# CPU_ROM.net
KiCad netlist of a schematic drawn in Altium Designer
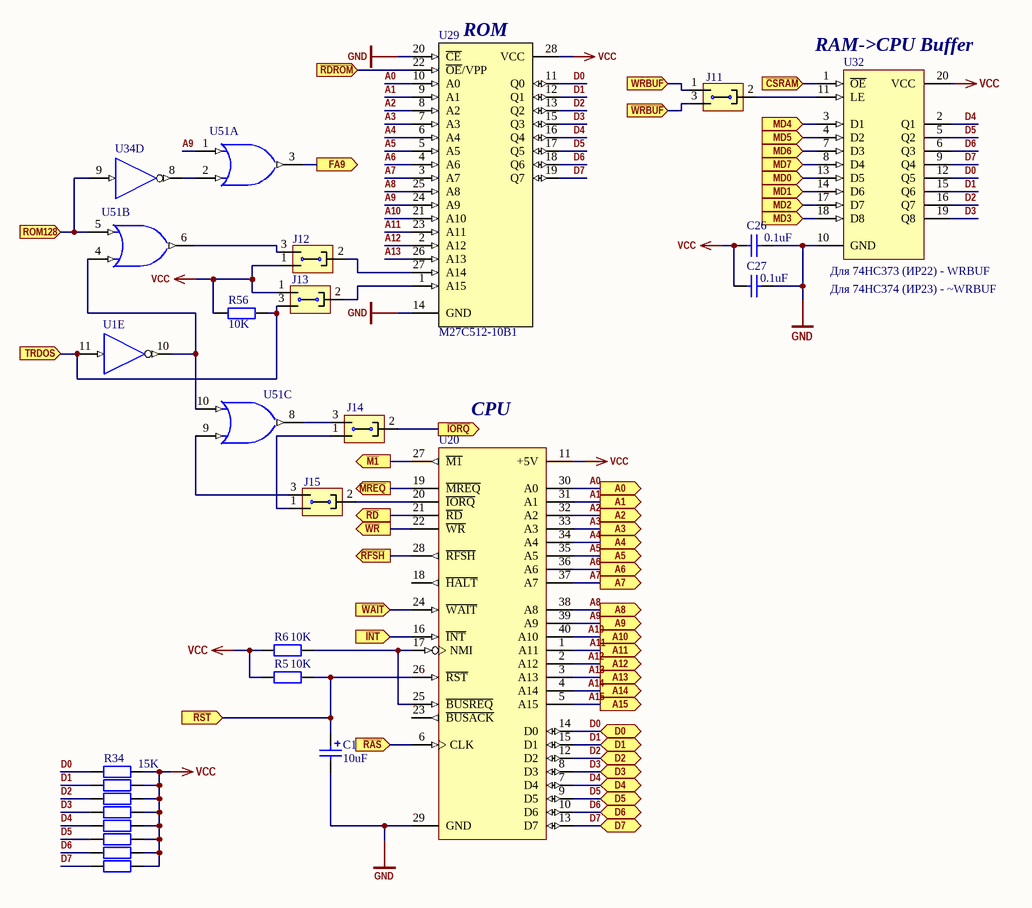
[diagram p0: CPU_ROM.SchDoc]

(export (version "E")
  (design (tool "Eeschema 10.0.6"))
  (components
    (comp (ref "C1")
      (value "10uF")
      (footprint "Lenin:JRB-5D")
      (description "Polarized Capacitor (Radial)")
      (fields (field (name "Comment") "Cap Pol1") (field (name "PUBLISHER") "Altium Limited"))
      (libsource (lib "Lenin") (part "Cap Pol1"))
    )
    (comp (ref "C26")
      (value "0.1uF")
      (footprint "RAD-0.3")
      (description "Capacitor")
      (fields (field (name "Comment") "Cap") (field (name "PUBLISHER") "Altium Limited"))
      (libsource (lib "Lenin") (part "Cap"))
    )
    (comp (ref "C27")
      (value "0.1uF")
      (footprint "RAD-0.3")
      (description "Capacitor")
      (fields (field (name "Comment") "Cap") (field (name "PUBLISHER") "Altium Limited"))
      (libsource (lib "Lenin") (part "Cap"))
    )
    (comp (ref "J11")
      (value "Jump3")
      (footprint "Miscellaneous Connectors:MHDR1X3")
      (libsource (lib "") (part "Jump3_1"))
    )
    (comp (ref "J12")
      (value "Jump3")
      (footprint "Miscellaneous Connectors:MHDR1X3")
      (libsource (lib "Lenin") (part "Jump3"))
    )
    (comp (ref "J13")
      (value "Jump3")
      (footprint "Miscellaneous Connectors:MHDR1X3")
      (libsource (lib "") (part "Jump3_1"))
    )
    (comp (ref "J14")
      (value "Jump3")
      (footprint "Miscellaneous Connectors:MHDR1X3")
      (libsource (lib "Lenin") (part "Jump3"))
    )
    (comp (ref "J15")
      (value "Jump3")
      (footprint "Miscellaneous Connectors:MHDR1X3")
      (libsource (lib "Lenin") (part "Jump3"))
    )
    (comp (ref "R5")
      (value "10K")
      (footprint "Lenin:AXIAL-0.4")
      (description "Resistor")
      (fields (field (name "PUBLISHER") "Altium Limited"))
      (libsource (lib "Lenin") (part "Res2"))
    )
    (comp (ref "R6")
      (value "10K")
      (footprint "Lenin:AXIAL-0.4")
      (description "Resistor")
      (fields (field (name "PUBLISHER") "Altium Limited"))
      (libsource (lib "") (part "Res2_1"))
    )
    (comp (ref "R34")
      (value "15K")
      (footprint "Lenin:AXIAL-0.4")
      (description "Resistor")
      (fields (field (name "PUBLISHER") "Altium Limited"))
      (libsource (lib "Lenin") (part "Res2"))
    )
    (comp (ref "R35")
      (value "~")
      (footprint "Lenin:AXIAL-0.4")
      (description "Resistor")
      (fields (field (name "PUBLISHER") "Altium Limited"))
      (libsource (lib "Lenin") (part "Res2"))
    )
    (comp (ref "R37")
      (value "~")
      (footprint "Lenin:AXIAL-0.4")
      (description "Resistor")
      (fields (field (name "PUBLISHER") "Altium Limited"))
      (libsource (lib "Lenin") (part "Res2"))
    )
    (comp (ref "R39")
      (value "~")
      (footprint "Lenin:AXIAL-0.4")
      (description "Resistor")
      (fields (field (name "PUBLISHER") "Altium Limited"))
      (libsource (lib "Lenin") (part "Res2"))
    )
    (comp (ref "R41")
      (value "~")
      (footprint "Lenin:AXIAL-0.4")
      (description "Resistor")
      (fields (field (name "PUBLISHER") "Altium Limited"))
      (libsource (lib "Lenin") (part "Res2"))
    )
    (comp (ref "R43")
      (value "~")
      (footprint "Lenin:AXIAL-0.4")
      (description "Resistor")
      (fields (field (name "PUBLISHER") "Altium Limited"))
      (libsource (lib "Lenin") (part "Res2"))
    )
    (comp (ref "R47")
      (value "~")
      (footprint "Lenin:AXIAL-0.4")
      (description "Resistor")
      (fields (field (name "PUBLISHER") "Altium Limited"))
      (libsource (lib "Lenin") (part "Res2"))
    )
    (comp (ref "R48")
      (value "~")
      (footprint "Lenin:AXIAL-0.4")
      (description "Resistor")
      (fields (field (name "PUBLISHER") "Altium Limited"))
      (libsource (lib "Lenin") (part "Res2"))
    )
    (comp (ref "R56")
      (value "10K")
      (footprint "Lenin:AXIAL-0.4")
      (description "Resistor")
      (fields (field (name "PUBLISHER") "Altium Limited"))
      (libsource (lib "Lenin") (part "Res2"))
    )
    (comp (ref "U1")
      (value "~")
      (footprint "N014")
      (description "Hex Inverter")
      (fields (field (name "PUBLISHER") "Altium Limited"))
      (libsource (lib "TI Logic Gate 2") (part "SN74HC04N"))
    )
    (comp (ref "U20")
      (value "Z84C0004PEC")
      (footprint "PDIP40")
      (description "CMOS 8-Bit Microprocessor")
      (fields (field (name "PUBLISHER") "Altium Limited"))
      (libsource (lib "Zilog Microprocessor 8-Bit") (part "Z84C0004PEC"))
    )
    (comp (ref "U29")
      (value "M27C512-10B1")
      (footprint "PDIP28")
      (description "512 Kbit (64Kb x 8) UV EPROM and OTP EPROM")
      (fields (field (name "PUBLISHER") "Altium Limited"))
      (libsource (lib "ST Memory EPROM 16-512 Kbit") (part "M27C512-10B1"))
    )
    (comp (ref "U32")
      (value "~")
      (footprint "N020")
      (description "Octal Transparent D-Type Latches with 3-State Outputs")
      (fields (field (name "PUBLISHER") "Altium Limited"))
      (libsource (lib "TI Logic Latch") (part "SN74HC373N"))
    )
    (comp (ref "U34")
      (value "~")
      (footprint "N014")
      (description "Hex Inverter")
      (fields (field (name "PUBLISHER") "Altium Limited"))
      (libsource (lib "TI Logic Gate 2") (part "SN74HC04N"))
    )
    (comp (ref "U51")
      (value "SN74HC32N")
      (footprint "N014")
      (description "Quadruple 2-Input Positive-OR Gate")
      (fields (field (name "PUBLISHER") "Altium Limited"))
      (libsource (lib "") (part "SN74HC32N_1"))
    )
  )
  (nets
    (net (code "1") (name "/A0") (class "Default")
      (node (ref "U20") (pin "30") (pinfunction "A0_30") (pintype "tri_state"))
      (node (ref "U29") (pin "10") (pinfunction "A0_10") (pintype "input"))
    )
    (net (code "2") (name "/A1") (class "Default")
      (node (ref "U20") (pin "31") (pinfunction "A1_31") (pintype "tri_state"))
      (node (ref "U29") (pin "9") (pinfunction "A1_9") (pintype "input"))
    )
    (net (code "3") (name "/A2") (class "Default")
      (node (ref "U20") (pin "32") (pinfunction "A2_32") (pintype "tri_state"))
      (node (ref "U29") (pin "8") (pinfunction "A2_8") (pintype "input"))
    )
    (net (code "4") (name "/A3") (class "Default")
      (node (ref "U20") (pin "33") (pinfunction "A3_33") (pintype "tri_state"))
      (node (ref "U29") (pin "7") (pinfunction "A3_7") (pintype "input"))
    )
    (net (code "5") (name "/A4") (class "Default")
      (node (ref "U20") (pin "34") (pinfunction "A4_34") (pintype "tri_state"))
      (node (ref "U29") (pin "6") (pinfunction "A4_6") (pintype "input"))
    )
    (net (code "6") (name "/A5") (class "Default")
      (node (ref "U20") (pin "35") (pinfunction "A5_35") (pintype "tri_state"))
      (node (ref "U29") (pin "5") (pinfunction "A5_5") (pintype "input"))
    )
    (net (code "7") (name "/A6") (class "Default")
      (node (ref "U20") (pin "36") (pinfunction "A6_36") (pintype "tri_state"))
      (node (ref "U29") (pin "4") (pinfunction "A6_4") (pintype "input"))
    )
    (net (code "8") (name "/A7") (class "Default")
      (node (ref "U20") (pin "37") (pinfunction "A7_37") (pintype "tri_state"))
      (node (ref "U29") (pin "3") (pinfunction "A7_3") (pintype "input"))
    )
    (net (code "9") (name "/A8") (class "Default")
      (node (ref "U20") (pin "38") (pinfunction "A8_38") (pintype "tri_state"))
      (node (ref "U29") (pin "25") (pinfunction "A8_25") (pintype "input"))
    )
    (net (code "10") (name "/A9") (class "Default")
      (node (ref "U20") (pin "39") (pinfunction "A9_39") (pintype "tri_state"))
      (node (ref "U29") (pin "24") (pinfunction "A9_24") (pintype "input"))
      (node (ref "U51") (pin "1") (pinfunction "A_1") (pintype "input"))
    )
    (net (code "11") (name "/A10") (class "Default")
      (node (ref "U20") (pin "40") (pinfunction "A10_40") (pintype "tri_state"))
      (node (ref "U29") (pin "21") (pinfunction "A10_21") (pintype "input"))
    )
    (net (code "12") (name "/A11") (class "Default")
      (node (ref "U20") (pin "1") (pinfunction "A11_1") (pintype "tri_state"))
      (node (ref "U29") (pin "23") (pinfunction "A11_23") (pintype "input"))
    )
    (net (code "13") (name "/A12") (class "Default")
      (node (ref "U20") (pin "2") (pinfunction "A12_2") (pintype "tri_state"))
      (node (ref "U29") (pin "2") (pinfunction "A12_2") (pintype "input"))
    )
    (net (code "14") (name "/A13") (class "Default")
      (node (ref "U20") (pin "3") (pinfunction "A13_3") (pintype "tri_state"))
      (node (ref "U29") (pin "26") (pinfunction "A13_26") (pintype "input"))
    )
    (net (code "15") (name "/A14") (class "Default")
      (node (ref "U20") (pin "4") (pinfunction "A14_4") (pintype "tri_state"))
    )
    (net (code "16") (name "/A15") (class "Default")
      (node (ref "U20") (pin "5") (pinfunction "A15_5") (pintype "tri_state"))
    )
    (net (code "17") (name "/D0") (class "Default")
      (node (ref "R34") (pin "1") (pinfunction "1_1") (pintype "passive"))
      (node (ref "U20") (pin "14") (pinfunction "D0_14") (pintype "bidirectional"))
      (node (ref "U29") (pin "11") (pinfunction "Q0_11") (pintype "bidirectional"))
      (node (ref "U32") (pin "12") (pinfunction "Q5_12") (pintype "tri_state"))
    )
    (net (code "18") (name "/D1") (class "Default")
      (node (ref "R35") (pin "1") (pinfunction "1_1") (pintype "passive"))
      (node (ref "U20") (pin "15") (pinfunction "D1_15") (pintype "bidirectional"))
      (node (ref "U29") (pin "12") (pinfunction "Q1_12") (pintype "bidirectional"))
      (node (ref "U32") (pin "15") (pinfunction "Q6_15") (pintype "tri_state"))
    )
    (net (code "19") (name "/D2") (class "Default")
      (node (ref "R37") (pin "1") (pinfunction "1_1") (pintype "passive"))
      (node (ref "U20") (pin "12") (pinfunction "D2_12") (pintype "bidirectional"))
      (node (ref "U29") (pin "13") (pinfunction "Q2_13") (pintype "bidirectional"))
      (node (ref "U32") (pin "16") (pinfunction "Q7_16") (pintype "tri_state"))
    )
    (net (code "20") (name "/D3") (class "Default")
      (node (ref "R39") (pin "1") (pinfunction "1_1") (pintype "passive"))
      (node (ref "U20") (pin "8") (pinfunction "D3_8") (pintype "bidirectional"))
      (node (ref "U29") (pin "15") (pinfunction "Q3_15") (pintype "bidirectional"))
      (node (ref "U32") (pin "19") (pinfunction "Q8_19") (pintype "tri_state"))
    )
    (net (code "21") (name "/D4") (class "Default")
      (node (ref "R41") (pin "1") (pinfunction "1_1") (pintype "passive"))
      (node (ref "U20") (pin "7") (pinfunction "D4_7") (pintype "bidirectional"))
      (node (ref "U29") (pin "16") (pinfunction "Q4_16") (pintype "bidirectional"))
      (node (ref "U32") (pin "2") (pinfunction "Q1_2") (pintype "tri_state"))
    )
    (net (code "22") (name "/D5") (class "Default")
      (node (ref "R43") (pin "1") (pinfunction "1_1") (pintype "passive"))
      (node (ref "U20") (pin "9") (pinfunction "D5_9") (pintype "bidirectional"))
      (node (ref "U29") (pin "17") (pinfunction "Q5_17") (pintype "bidirectional"))
      (node (ref "U32") (pin "5") (pinfunction "Q2_5") (pintype "tri_state"))
    )
    (net (code "23") (name "/D6") (class "Default")
      (node (ref "R47") (pin "1") (pinfunction "1_1") (pintype "passive"))
      (node (ref "U20") (pin "10") (pinfunction "D6_10") (pintype "bidirectional"))
      (node (ref "U29") (pin "18") (pinfunction "Q6_18") (pintype "bidirectional"))
      (node (ref "U32") (pin "6") (pinfunction "Q3_6") (pintype "tri_state"))
    )
    (net (code "24") (name "/D7") (class "Default")
      (node (ref "R48") (pin "1") (pinfunction "1_1") (pintype "passive"))
      (node (ref "U20") (pin "13") (pinfunction "D7_13") (pintype "bidirectional"))
      (node (ref "U29") (pin "19") (pinfunction "Q7_19") (pintype "bidirectional"))
      (node (ref "U32") (pin "9") (pinfunction "Q4_9") (pintype "tri_state"))
    )
    (net (code "25") (name "/FA9") (class "Default")
      (node (ref "U51") (pin "3") (pinfunction "Y_3") (pintype "output"))
    )
    (net (code "26") (name "/MD0") (class "Default")
      (node (ref "U32") (pin "13") (pinfunction "D5_13") (pintype "input"))
    )
    (net (code "27") (name "/MD1") (class "Default")
      (node (ref "U32") (pin "14") (pinfunction "D6_14") (pintype "input"))
    )
    (net (code "28") (name "/MD2") (class "Default")
      (node (ref "U32") (pin "17") (pinfunction "D7_17") (pintype "input"))
    )
    (net (code "29") (name "/MD3") (class "Default")
      (node (ref "U32") (pin "18") (pinfunction "D8_18") (pintype "input"))
    )
    (net (code "30") (name "/MD4") (class "Default")
      (node (ref "U32") (pin "3") (pinfunction "D1_3") (pintype "input"))
    )
    (net (code "31") (name "/MD5") (class "Default")
      (node (ref "U32") (pin "4") (pinfunction "D2_4") (pintype "input"))
    )
    (net (code "32") (name "/MD6") (class "Default")
      (node (ref "U32") (pin "7") (pinfunction "D3_7") (pintype "input"))
    )
    (net (code "33") (name "/MD7") (class "Default")
      (node (ref "U32") (pin "8") (pinfunction "D4_8") (pintype "input"))
    )
    (net (code "34") (name "/ROM128") (class "Default")
      (node (ref "U34") (pin "9") (pinfunction "A_9") (pintype "input"))
      (node (ref "U51") (pin "5") (pinfunction "B_5") (pintype "input"))
    )
    (net (code "35") (name "/TRDOS") (class "Default")
      (node (ref "J13") (pin "3") (pintype "passive"))
      (node (ref "R56") (pin "2") (pinfunction "2_2") (pintype "passive"))
      (node (ref "U1") (pin "11") (pinfunction "A_11") (pintype "input"))
    )
    (net (code "36") (name "/WRBUF") (class "Default") (node (ref "J11") (pin "1") (pintype "passive")))
    (net (code "37") (name "/~{CSRAM}") (class "Default")
      (node (ref "U32") (pin "1") (pinfunction "~{OE}_1") (pintype "input"))
    )
    (net (code "38") (name "/~{INT}") (class "Default")
      (node (ref "U20") (pin "16") (pinfunction "~{INT}_16") (pintype "input"))
    )
    (net (code "39") (name "/~{IORQ}") (class "Default") (node (ref "J14") (pin "2") (pintype "passive")))
    (net (code "40") (name "/~{M1}") (class "Default")
      (node (ref "U20") (pin "27") (pinfunction "~{M1}_27") (pintype "output"))
    )
    (net (code "41") (name "/~{MREQ}") (class "Default")
      (node (ref "U20") (pin "19") (pinfunction "~{MREQ}_19") (pintype "tri_state"))
    )
    (net (code "42") (name "/~{RAS}") (class "Default")
      (node (ref "U20") (pin "6") (pinfunction "CLK_6") (pintype "input"))
    )
    (net (code "43") (name "/~{RDROM}") (class "Default")
      (node (ref "U29") (pin "22") (pinfunction "~{OE}/VPP_22") (pintype "input"))
    )
    (net (code "44") (name "/~{RD}") (class "Default")
      (node (ref "U20") (pin "21") (pinfunction "~{RD}_21") (pintype "tri_state"))
    )
    (net (code "45") (name "/~{RFSH}") (class "Default")
      (node (ref "U20") (pin "28") (pinfunction "~{RFSH}_28") (pintype "output"))
    )
    (net (code "46") (name "/~{RST}") (class "Default")
      (node (ref "C1") (pin "1") (pinfunction "1_1") (pintype "passive"))
      (node (ref "R5") (pin "2") (pinfunction "2_2") (pintype "passive"))
      (node (ref "U20") (pin "26") (pinfunction "~{RST}_26") (pintype "input"))
    )
    (net (code "47") (name "/~{WAIT}") (class "Default")
      (node (ref "U20") (pin "24") (pinfunction "~{WAIT}_24") (pintype "input"))
    )
    (net (code "48") (name "/~{WRBUF}") (class "Default") (node (ref "J11") (pin "3") (pintype "passive")))
    (net (code "49") (name "/~{WR}") (class "Default")
      (node (ref "U20") (pin "22") (pinfunction "~{WR}_22") (pintype "tri_state"))
    )
    (net (code "50") (name "GND") (class "Default")
      (node (ref "C1") (pin "2") (pinfunction "2_2") (pintype "passive"))
      (node (ref "C26") (pin "2") (pinfunction "2_2") (pintype "passive"))
      (node (ref "C27") (pin "2") (pinfunction "2_2") (pintype "passive"))
      (node (ref "U1") (pin "7") (pinfunction "GND_7") (pintype "power_in"))
      (node (ref "U20") (pin "29") (pinfunction "GND_29") (pintype "power_in"))
      (node (ref "U29") (pin "14") (pinfunction "GND_14") (pintype "power_in"))
      (node (ref "U29") (pin "20") (pinfunction "~{CE}_20") (pintype "input"))
      (node (ref "U32") (pin "10") (pinfunction "GND_10") (pintype "power_in"))
      (node (ref "U34") (pin "7") (pinfunction "GND_7") (pintype "power_in"))
      (node (ref "U51") (pin "7") (pinfunction "GND_7") (pintype "power_in"))
    )
    (net (code "51") (name "Net-(J14-Pad1)") (class "Default")
      (node (ref "J14") (pin "1") (pintype "passive"))
      (node (ref "J15") (pin "1") (pintype "passive"))
    )
    (net (code "52") (name "Net-(U1E-Y)") (class "Default")
      (node (ref "U1") (pin "10") (pinfunction "Y_10") (pintype "output"))
      (node (ref "U51") (pin "10") (pinfunction "B_10") (pintype "input"))
      (node (ref "U51") (pin "4") (pinfunction "A_4") (pintype "input"))
    )
    (net (code "53") (name "Net-(U20-NMI)") (class "Default")
      (node (ref "R6") (pin "1") (pinfunction "1_1") (pintype "passive"))
      (node (ref "U20") (pin "17") (pinfunction "NMI_17") (pintype "input"))
      (node (ref "U20") (pin "25") (pinfunction "~{BUSREQ}_25") (pintype "input"))
    )
    (net (code "54") (name "Net-(U20-~{IORQ})") (class "Default")
      (node (ref "J15") (pin "2") (pintype "passive"))
      (node (ref "U20") (pin "20") (pinfunction "~{IORQ}_20") (pintype "tri_state"))
    )
    (net (code "55") (name "Net-(U29-A14)") (class "Default")
      (node (ref "J12") (pin "2") (pintype "passive"))
      (node (ref "U29") (pin "27") (pinfunction "A14_27") (pintype "input"))
    )
    (net (code "56") (name "Net-(U29-A15)") (class "Default")
      (node (ref "J13") (pin "2") (pintype "passive"))
      (node (ref "U29") (pin "1") (pinfunction "A15_1") (pintype "input"))
    )
    (net (code "57") (name "Net-(U32-LE)") (class "Default")
      (node (ref "J11") (pin "2") (pintype "passive"))
      (node (ref "U32") (pin "11") (pinfunction "LE_11") (pintype "input"))
    )
    (net (code "58") (name "Net-(U34D-Y)") (class "Default")
      (node (ref "U34") (pin "8") (pinfunction "Y_8") (pintype "output"))
      (node (ref "U51") (pin "2") (pinfunction "B_2") (pintype "input"))
    )
    (net (code "59") (name "Net-(U51B-Y)") (class "Default")
      (node (ref "J12") (pin "3") (pintype "passive"))
      (node (ref "U51") (pin "6") (pinfunction "Y_6") (pintype "output"))
    )
    (net (code "60") (name "Net-(U51C-A)") (class "Default")
      (node (ref "J15") (pin "3") (pintype "passive"))
      (node (ref "U51") (pin "9") (pinfunction "A_9") (pintype "input"))
    )
    (net (code "61") (name "Net-(U51C-Y)") (class "Default")
      (node (ref "J14") (pin "3") (pintype "passive"))
      (node (ref "U51") (pin "8") (pinfunction "Y_8") (pintype "output"))
    )
    (net (code "62") (name "VCC") (class "Default")
      (node (ref "C26") (pin "1") (pinfunction "1_1") (pintype "passive"))
      (node (ref "C27") (pin "1") (pinfunction "1_1") (pintype "passive"))
      (node (ref "J12") (pin "1") (pintype "passive"))
      (node (ref "J13") (pin "1") (pintype "passive"))
      (node (ref "R34") (pin "2") (pinfunction "2_2") (pintype "passive"))
      (node (ref "R35") (pin "2") (pinfunction "2_2") (pintype "passive"))
      (node (ref "R37") (pin "2") (pinfunction "2_2") (pintype "passive"))
      (node (ref "R39") (pin "2") (pinfunction "2_2") (pintype "passive"))
      (node (ref "R41") (pin "2") (pinfunction "2_2") (pintype "passive"))
      (node (ref "R43") (pin "2") (pinfunction "2_2") (pintype "passive"))
      (node (ref "R47") (pin "2") (pinfunction "2_2") (pintype "passive"))
      (node (ref "R48") (pin "2") (pinfunction "2_2") (pintype "passive"))
      (node (ref "R5") (pin "1") (pinfunction "1_1") (pintype "passive"))
      (node (ref "R56") (pin "1") (pinfunction "1_1") (pintype "passive"))
      (node (ref "R6") (pin "2") (pinfunction "2_2") (pintype "passive"))
      (node (ref "U1") (pin "14") (pinfunction "VCC_14") (pintype "power_in"))
      (node (ref "U20") (pin "11") (pinfunction "+5V_11") (pintype "power_in"))
      (node (ref "U29") (pin "28") (pinfunction "VCC_28") (pintype "power_in"))
      (node (ref "U32") (pin "20") (pinfunction "VCC_20") (pintype "power_in"))
      (node (ref "U34") (pin "14") (pinfunction "VCC_14") (pintype "power_in"))
      (node (ref "U51") (pin "14") (pinfunction "VCC_14") (pintype "power_in"))
    )
    (net (code "63") (name "unconnected-(U20-~{BUSACK}-Pad23)") (class "Default")
      (node (ref "U20") (pin "23") (pinfunction "~{BUSACK}_23") (pintype "output"))
    )
    (net (code "64") (name "unconnected-(U20-~{HALT}-Pad18)") (class "Default")
      (node (ref "U20") (pin "18") (pinfunction "~{HALT}_18") (pintype "output"))
    )
  )
)
